# 1_P1.net
KiCad netlist of a schematic drawn in Altium Designer
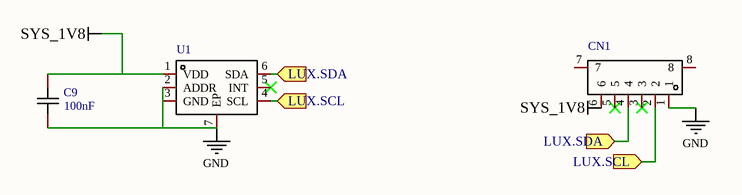
[diagram p0: 1_P1.schdoc]

(export (version "E")
  (design (tool "Eeschema 10.0.6"))
  (components
    (comp (ref "C9")
      (value "100nF")
      (fields
        (field (name "NAME") "100nF")
        (field (name "MANUFACTURER") "YAGEO")
        (field (name "MANUFACTURER PART") "CC0603KRX7R9BB104")
      )
      (libsource (lib "altium-import") (part "root_3_CC0603KRX7R9BB104_"))
    )
    (comp (ref "CN1")
      (value "532610671")
      (fields (field (name "MANUFACTURER") "MOLEX"))
      (libsource (lib "altium-import") (part "root_1_mirrored_532610671_"))
    )
    (comp (ref "U1")
      (value "OPT3001DNPR")
      (fields (field (name "MANUFACTURER") "TI(德州仪器)"))
      (libsource (lib "altium-import") (part "root_0_OPT3001DNPR_"))
    )
  )
  (nets
    (net (code "1") (name "/LUX.SCL") (class "Default")
      (node (ref "CN1") (pin "2") (pinfunction "2_2") (pintype "passive"))
      (node (ref "U1") (pin "4") (pinfunction "SCL_4") (pintype "passive"))
    )
    (net (code "2") (name "/LUX.SDA") (class "Default")
      (node (ref "CN1") (pin "4") (pinfunction "4_4") (pintype "passive"))
      (node (ref "U1") (pin "6") (pinfunction "SDA_6") (pintype "passive"))
    )
    (net (code "3") (name "GND") (class "Default")
      (node (ref "C9") (pin "2") (pinfunction "2_2") (pintype "passive"))
      (node (ref "CN1") (pin "1") (pinfunction "1_1") (pintype "passive"))
      (node (ref "U1") (pin "2") (pinfunction "ADDR_2") (pintype "passive"))
      (node (ref "U1") (pin "3") (pinfunction "GND_3") (pintype "passive"))
      (node (ref "U1") (pin "7") (pinfunction "EP_7") (pintype "passive"))
    )
    (net (code "4") (name "SYS_1V8") (class "Default")
      (node (ref "C9") (pin "1") (pinfunction "1_1") (pintype "passive"))
      (node (ref "CN1") (pin "6") (pinfunction "6_6") (pintype "passive"))
      (node (ref "U1") (pin "1") (pinfunction "VDD_1") (pintype "passive"))
    )
    (net (code "5") (name "unconnected-(CN1-Pad3)") (class "Default")
      (node (ref "CN1") (pin "3") (pinfunction "3_3") (pintype "passive+no_connect"))
    )
    (net (code "6") (name "unconnected-(CN1-Pad5)") (class "Default")
      (node (ref "CN1") (pin "5") (pinfunction "5_5") (pintype "passive+no_connect"))
    )
    (net (code "7") (name "unconnected-(CN1-Pad7)") (class "Default")
      (node (ref "CN1") (pin "7") (pinfunction "7_7") (pintype "passive"))
    )
    (net (code "8") (name "unconnected-(CN1-Pad8)") (class "Default")
      (node (ref "CN1") (pin "8") (pinfunction "8_8") (pintype "passive"))
    )
    (net (code "9") (name "unconnected-(U1-INT-Pad5)") (class "Default")
      (node (ref "U1") (pin "5") (pinfunction "INT_5") (pintype "passive+no_connect"))
    )
  )
)
